# rx08-vrs.net
KiCad netlist of a schematic drawn in EAGLE
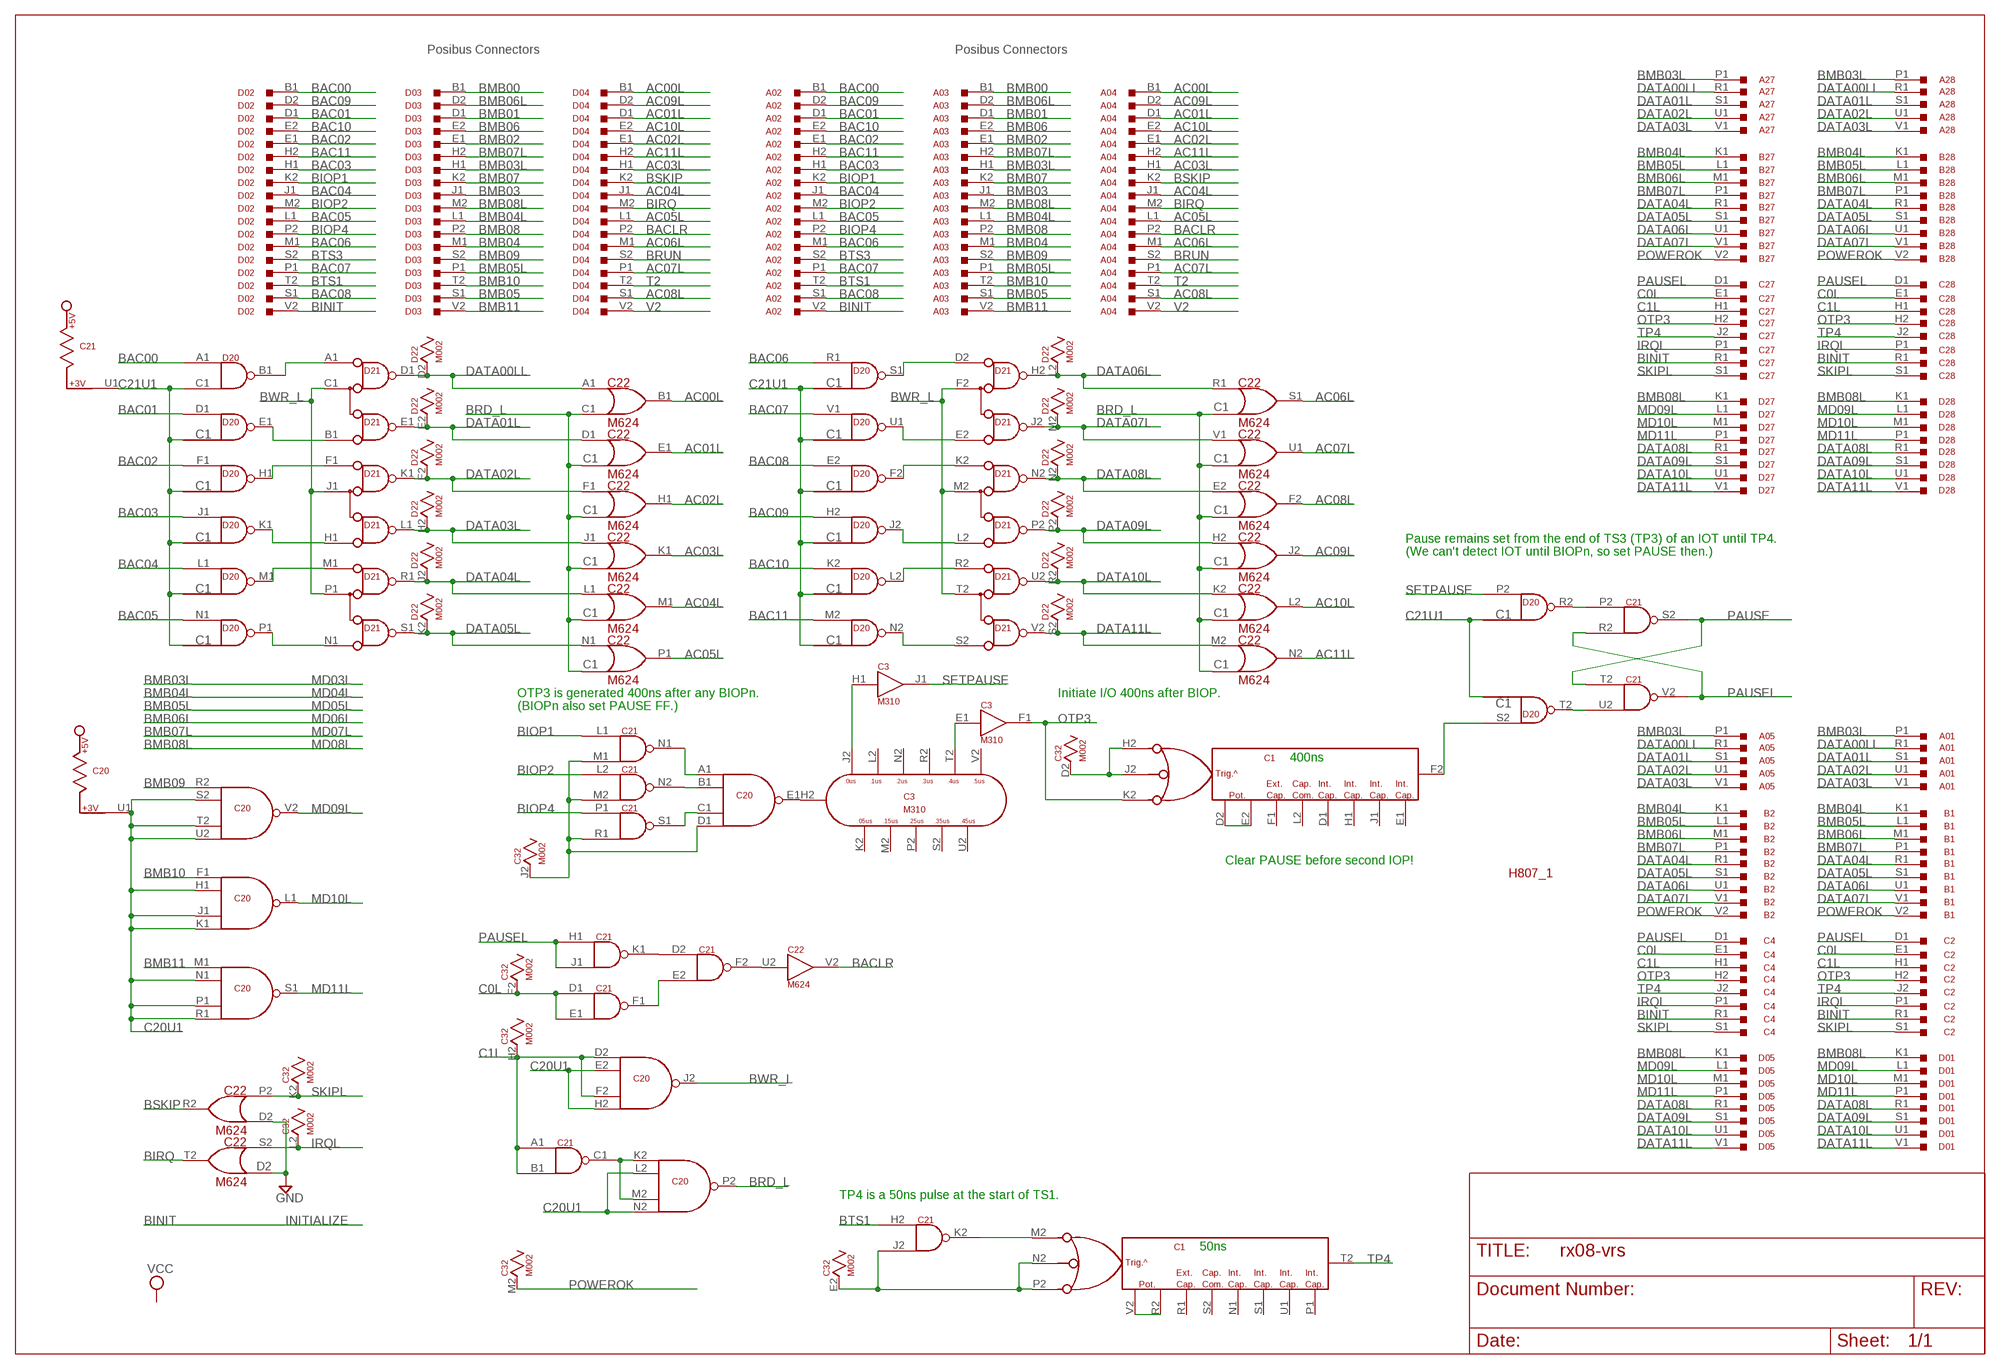
[diagram p0: schematic, sheet 1]

(export (version "E")
  (design (tool "Eeschema 10.0.6"))
  (components
    (comp (ref "A01")
      (value "M916")
      (footprint "eagle-import:H807")
      (libsource (lib "eagle-import") (part "M916"))
    )
    (comp (ref "A02")
      (value "M903")
      (footprint "eagle-import:H807")
      (libsource (lib "eagle-import") (part "M903"))
    )
    (comp (ref "A03")
      (value "M903")
      (footprint "eagle-import:H807")
      (libsource (lib "eagle-import") (part "M903"))
    )
    (comp (ref "A04")
      (value "M903")
      (footprint "eagle-import:H807")
      (libsource (lib "eagle-import") (part "M903"))
    )
    (comp (ref "A05")
      (value "M916")
      (footprint "eagle-import:H807")
      (libsource (lib "eagle-import") (part "M916"))
    )
    (comp (ref "A27")
      (value "M916")
      (footprint "eagle-import:H807")
      (libsource (lib "eagle-import") (part "M916"))
    )
    (comp (ref "A28")
      (value "M916")
      (footprint "eagle-import:H807")
      (libsource (lib "eagle-import") (part "M916"))
    )
    (comp (ref "B1")
      (value "M916")
      (footprint "eagle-import:H807")
      (libsource (lib "eagle-import") (part "M916"))
    )
    (comp (ref "B2")
      (value "M916")
      (footprint "eagle-import:H807")
      (libsource (lib "eagle-import") (part "M916"))
    )
    (comp (ref "B27")
      (value "M916")
      (footprint "eagle-import:H807")
      (libsource (lib "eagle-import") (part "M916"))
    )
    (comp (ref "B28")
      (value "M916")
      (footprint "eagle-import:H807")
      (libsource (lib "eagle-import") (part "M916"))
    )
    (comp (ref "C1")
      (value "M302")
      (footprint "eagle-import:H807")
      (libsource (lib "eagle-import") (part "M302"))
    )
    (comp (ref "C2")
      (value "M916")
      (footprint "eagle-import:H807")
      (libsource (lib "eagle-import") (part "M916"))
    )
    (comp (ref "C3")
      (value "M310")
      (footprint "eagle-import:H807")
      (libsource (lib "eagle-import") (part "M310"))
    )
    (comp (ref "C4")
      (value "M916")
      (footprint "eagle-import:H807")
      (libsource (lib "eagle-import") (part "M916"))
    )
    (comp (ref "C20")
      (value "M617")
      (footprint "eagle-import:H807")
      (libsource (lib "eagle-import") (part "M617"))
    )
    (comp (ref "C21")
      (value "M113")
      (footprint "eagle-import:H807")
      (libsource (lib "eagle-import") (part "M113"))
    )
    (comp (ref "C22")
      (value "M624")
      (footprint "eagle-import:H807")
      (libsource (lib "eagle-import") (part "M624"))
    )
    (comp (ref "C27")
      (value "M916")
      (footprint "eagle-import:H807")
      (libsource (lib "eagle-import") (part "M916"))
    )
    (comp (ref "C28")
      (value "M916")
      (footprint "eagle-import:H807")
      (libsource (lib "eagle-import") (part "M916"))
    )
    (comp (ref "C32")
      (value "M002")
      (footprint "eagle-import:H807")
      (libsource (lib "eagle-import") (part "M002"))
    )
    (comp (ref "D01")
      (value "M916")
      (footprint "eagle-import:H807")
      (libsource (lib "eagle-import") (part "M916"))
    )
    (comp (ref "D02")
      (value "M903")
      (footprint "eagle-import:H807")
      (libsource (lib "eagle-import") (part "M903"))
    )
    (comp (ref "D03")
      (value "M903")
      (footprint "eagle-import:H807")
      (libsource (lib "eagle-import") (part "M903"))
    )
    (comp (ref "D04")
      (value "M903")
      (footprint "eagle-import:H807")
      (libsource (lib "eagle-import") (part "M903"))
    )
    (comp (ref "D05")
      (value "M916")
      (footprint "eagle-import:H807")
      (libsource (lib "eagle-import") (part "M916"))
    )
    (comp (ref "D20")
      (value "M101")
      (footprint "eagle-import:H807")
      (libsource (lib "eagle-import") (part "M101"))
    )
    (comp (ref "D21")
      (value "M623")
      (footprint "eagle-import:H807")
      (libsource (lib "eagle-import") (part "M623"))
    )
    (comp (ref "D22")
      (value "M002")
      (footprint "eagle-import:H807")
      (libsource (lib "eagle-import") (part "M002"))
    )
    (comp (ref "D27")
      (value "M916")
      (footprint "eagle-import:H807")
      (libsource (lib "eagle-import") (part "M916"))
    )
    (comp (ref "D28")
      (value "M916")
      (footprint "eagle-import:H807")
      (libsource (lib "eagle-import") (part "M916"))
    )
    (comp (ref "H807_1")
      (value "H807")
      (footprint "eagle-import:H807")
      (libsource (lib "eagle-import") (part "H807"))
    )
  )
  (nets
    (net (code "1") (name "/AC00L") (class "Default")
      (node (ref "A04") (pin "B1") (pinfunction "P$2_B1") (pintype "bidirectional"))
      (node (ref "C22") (pin "B1") (pinfunction "OUT_B1") (pintype "output"))
      (node (ref "D04") (pin "B1") (pinfunction "P$2_B1") (pintype "bidirectional"))
    )
    (net (code "2") (name "/AC01L") (class "Default")
      (node (ref "A04") (pin "D1") (pinfunction "P$2_D1") (pintype "bidirectional"))
      (node (ref "C22") (pin "E1") (pinfunction "OUT_E1") (pintype "output"))
      (node (ref "D04") (pin "D1") (pinfunction "P$2_D1") (pintype "bidirectional"))
    )
    (net (code "3") (name "/AC02L") (class "Default")
      (node (ref "A04") (pin "E1") (pinfunction "P$2_E1") (pintype "bidirectional"))
      (node (ref "C22") (pin "H1") (pinfunction "OUT_H1") (pintype "output"))
      (node (ref "D04") (pin "E1") (pinfunction "P$2_E1") (pintype "bidirectional"))
    )
    (net (code "4") (name "/AC03L") (class "Default")
      (node (ref "A04") (pin "H1") (pinfunction "P$2_H1") (pintype "bidirectional"))
      (node (ref "C22") (pin "K1") (pinfunction "OUT_K1") (pintype "output"))
      (node (ref "D04") (pin "H1") (pinfunction "P$2_H1") (pintype "bidirectional"))
    )
    (net (code "5") (name "/AC04L") (class "Default")
      (node (ref "A04") (pin "J1") (pinfunction "P$2_J1") (pintype "bidirectional"))
      (node (ref "C22") (pin "M1") (pinfunction "OUT_M1") (pintype "output"))
      (node (ref "D04") (pin "J1") (pinfunction "P$2_J1") (pintype "bidirectional"))
    )
    (net (code "6") (name "/AC05L") (class "Default")
      (node (ref "A04") (pin "L1") (pinfunction "P$2_L1") (pintype "bidirectional"))
      (node (ref "C22") (pin "P1") (pinfunction "OUT_P1") (pintype "output"))
      (node (ref "D04") (pin "L1") (pinfunction "P$2_L1") (pintype "bidirectional"))
    )
    (net (code "7") (name "/AC06L") (class "Default")
      (node (ref "A04") (pin "M1") (pinfunction "P$2_M1") (pintype "bidirectional"))
      (node (ref "C22") (pin "S1") (pinfunction "OUT_S1") (pintype "output"))
      (node (ref "D04") (pin "M1") (pinfunction "P$2_M1") (pintype "bidirectional"))
    )
    (net (code "8") (name "/AC07L") (class "Default")
      (node (ref "A04") (pin "P1") (pinfunction "P$2_P1") (pintype "bidirectional"))
      (node (ref "C22") (pin "U1") (pinfunction "OUT_U1") (pintype "output"))
      (node (ref "D04") (pin "P1") (pinfunction "P$2_P1") (pintype "bidirectional"))
    )
    (net (code "9") (name "/AC08L") (class "Default")
      (node (ref "A04") (pin "S1") (pinfunction "P$2_S1") (pintype "bidirectional"))
      (node (ref "C22") (pin "F2") (pinfunction "OUT_F2") (pintype "output"))
      (node (ref "D04") (pin "S1") (pinfunction "P$2_S1") (pintype "bidirectional"))
    )
    (net (code "10") (name "/AC09L") (class "Default")
      (node (ref "A04") (pin "D2") (pinfunction "P$2_D2") (pintype "bidirectional"))
      (node (ref "C22") (pin "J2") (pinfunction "OUT_J2") (pintype "output"))
      (node (ref "D04") (pin "D2") (pinfunction "P$2_D2") (pintype "bidirectional"))
    )
    (net (code "11") (name "/AC10L") (class "Default")
      (node (ref "A04") (pin "E2") (pinfunction "P$2_E2") (pintype "bidirectional"))
      (node (ref "C22") (pin "L2") (pinfunction "OUT_L2") (pintype "output"))
      (node (ref "D04") (pin "E2") (pinfunction "P$2_E2") (pintype "bidirectional"))
    )
    (net (code "12") (name "/AC11L") (class "Default")
      (node (ref "A04") (pin "H2") (pinfunction "P$2_H2") (pintype "bidirectional"))
      (node (ref "C22") (pin "N2") (pinfunction "OUT_N2") (pintype "output"))
      (node (ref "D04") (pin "H2") (pinfunction "P$2_H2") (pintype "bidirectional"))
    )
    (net (code "13") (name "/BAC00") (class "Default")
      (node (ref "A02") (pin "B1") (pinfunction "P$2_B1") (pintype "bidirectional"))
      (node (ref "D02") (pin "B1") (pinfunction "P$2_B1") (pintype "bidirectional"))
      (node (ref "D20") (pin "A1") (pinfunction "IN1_A1") (pintype "input"))
    )
    (net (code "14") (name "/BAC01") (class "Default")
      (node (ref "A02") (pin "D1") (pinfunction "P$2_D1") (pintype "bidirectional"))
      (node (ref "D02") (pin "D1") (pinfunction "P$2_D1") (pintype "bidirectional"))
      (node (ref "D20") (pin "D1") (pinfunction "IN_D1") (pintype "input"))
    )
    (net (code "15") (name "/BAC02") (class "Default")
      (node (ref "A02") (pin "E1") (pinfunction "P$2_E1") (pintype "bidirectional"))
      (node (ref "D02") (pin "E1") (pinfunction "P$2_E1") (pintype "bidirectional"))
      (node (ref "D20") (pin "F1") (pinfunction "IN_F1") (pintype "input"))
    )
    (net (code "16") (name "/BAC03") (class "Default")
      (node (ref "A02") (pin "H1") (pinfunction "P$2_H1") (pintype "bidirectional"))
      (node (ref "D02") (pin "H1") (pinfunction "P$2_H1") (pintype "bidirectional"))
      (node (ref "D20") (pin "J1") (pinfunction "IN_J1") (pintype "input"))
    )
    (net (code "17") (name "/BAC04") (class "Default")
      (node (ref "A02") (pin "J1") (pinfunction "P$2_J1") (pintype "bidirectional"))
      (node (ref "D02") (pin "J1") (pinfunction "P$2_J1") (pintype "bidirectional"))
      (node (ref "D20") (pin "L1") (pinfunction "IN_L1") (pintype "input"))
    )
    (net (code "18") (name "/BAC05") (class "Default")
      (node (ref "A02") (pin "L1") (pinfunction "P$2_L1") (pintype "bidirectional"))
      (node (ref "D02") (pin "L1") (pinfunction "P$2_L1") (pintype "bidirectional"))
      (node (ref "D20") (pin "N1") (pinfunction "IN_N1") (pintype "input"))
    )
    (net (code "19") (name "/BAC06") (class "Default")
      (node (ref "A02") (pin "M1") (pinfunction "P$2_M1") (pintype "bidirectional"))
      (node (ref "D02") (pin "M1") (pinfunction "P$2_M1") (pintype "bidirectional"))
      (node (ref "D20") (pin "R1") (pinfunction "IN_R1") (pintype "input"))
    )
    (net (code "20") (name "/BAC07") (class "Default")
      (node (ref "A02") (pin "P1") (pinfunction "P$2_P1") (pintype "bidirectional"))
      (node (ref "D02") (pin "P1") (pinfunction "P$2_P1") (pintype "bidirectional"))
      (node (ref "D20") (pin "V1") (pinfunction "IN_V1") (pintype "input"))
    )
    (net (code "21") (name "/BAC08") (class "Default")
      (node (ref "A02") (pin "S1") (pinfunction "P$2_S1") (pintype "bidirectional"))
      (node (ref "D02") (pin "S1") (pinfunction "P$2_S1") (pintype "bidirectional"))
      (node (ref "D20") (pin "E2") (pinfunction "IN_E2") (pintype "input"))
    )
    (net (code "22") (name "/BAC09") (class "Default")
      (node (ref "A02") (pin "D2") (pinfunction "P$2_D2") (pintype "bidirectional"))
      (node (ref "D02") (pin "D2") (pinfunction "P$2_D2") (pintype "bidirectional"))
      (node (ref "D20") (pin "H2") (pinfunction "IN_H2") (pintype "input"))
    )
    (net (code "23") (name "/BAC10") (class "Default")
      (node (ref "A02") (pin "E2") (pinfunction "P$2_E2") (pintype "bidirectional"))
      (node (ref "D02") (pin "E2") (pinfunction "P$2_E2") (pintype "bidirectional"))
      (node (ref "D20") (pin "K2") (pinfunction "IN_K2") (pintype "input"))
    )
    (net (code "24") (name "/BAC11") (class "Default")
      (node (ref "A02") (pin "H2") (pinfunction "P$2_H2") (pintype "bidirectional"))
      (node (ref "D02") (pin "H2") (pinfunction "P$2_H2") (pintype "bidirectional"))
      (node (ref "D20") (pin "M2") (pinfunction "IN_M2") (pintype "input"))
    )
    (net (code "25") (name "/BACLR") (class "Default")
      (node (ref "A04") (pin "P2") (pinfunction "P$2_P2") (pintype "bidirectional"))
      (node (ref "C22") (pin "V2") (pinfunction "OUT_V2") (pintype "output"))
      (node (ref "D04") (pin "P2") (pinfunction "P$2_P2") (pintype "bidirectional"))
    )
    (net (code "26") (name "/BINIT") (class "Default")
      (node (ref "A02") (pin "V2") (pinfunction "P$2_V2") (pintype "bidirectional"))
      (node (ref "C2") (pin "R1") (pinfunction "P$2_R1") (pintype "bidirectional"))
      (node (ref "C27") (pin "R1") (pinfunction "P$2_R1") (pintype "bidirectional"))
      (node (ref "C28") (pin "R1") (pinfunction "P$2_R1") (pintype "bidirectional"))
      (node (ref "C4") (pin "R1") (pinfunction "P$2_R1") (pintype "bidirectional"))
      (node (ref "D02") (pin "V2") (pinfunction "P$2_V2") (pintype "bidirectional"))
    )
    (net (code "27") (name "/BIOP1") (class "Default")
      (node (ref "A02") (pin "K2") (pinfunction "P$2_K2") (pintype "bidirectional"))
      (node (ref "C21") (pin "L1") (pinfunction "IN1_L1") (pintype "input"))
      (node (ref "D02") (pin "K2") (pinfunction "P$2_K2") (pintype "bidirectional"))
    )
    (net (code "28") (name "/BIOP2") (class "Default")
      (node (ref "A02") (pin "M2") (pinfunction "P$2_M2") (pintype "bidirectional"))
      (node (ref "C21") (pin "L2") (pinfunction "IN1_L2") (pintype "input"))
      (node (ref "D02") (pin "M2") (pinfunction "P$2_M2") (pintype "bidirectional"))
    )
    (net (code "29") (name "/BIOP4") (class "Default")
      (node (ref "A02") (pin "P2") (pinfunction "P$2_P2") (pintype "bidirectional"))
      (node (ref "C21") (pin "P1") (pinfunction "IN1_P1") (pintype "input"))
      (node (ref "D02") (pin "P2") (pinfunction "P$2_P2") (pintype "bidirectional"))
    )
    (net (code "30") (name "/BIRQ") (class "Default")
      (node (ref "A04") (pin "M2") (pinfunction "P$2_M2") (pintype "bidirectional"))
      (node (ref "C22") (pin "T2") (pinfunction "OUT_T2") (pintype "output"))
      (node (ref "D04") (pin "M2") (pinfunction "P$2_M2") (pintype "bidirectional"))
    )
    (net (code "31") (name "/BMB00") (class "Default")
      (node (ref "A03") (pin "B1") (pinfunction "P$2_B1") (pintype "bidirectional"))
      (node (ref "D03") (pin "B1") (pinfunction "P$2_B1") (pintype "bidirectional"))
    )
    (net (code "32") (name "/BMB01") (class "Default")
      (node (ref "A03") (pin "D1") (pinfunction "P$2_D1") (pintype "bidirectional"))
      (node (ref "D03") (pin "D1") (pinfunction "P$2_D1") (pintype "bidirectional"))
    )
    (net (code "33") (name "/BMB02") (class "Default")
      (node (ref "A03") (pin "E1") (pinfunction "P$2_E1") (pintype "bidirectional"))
      (node (ref "D03") (pin "E1") (pinfunction "P$2_E1") (pintype "bidirectional"))
    )
    (net (code "34") (name "/BMB03") (class "Default")
      (node (ref "A03") (pin "J1") (pinfunction "P$2_J1") (pintype "bidirectional"))
      (node (ref "D03") (pin "J1") (pinfunction "P$2_J1") (pintype "bidirectional"))
    )
    (net (code "35") (name "/BMB03L") (class "Default")
      (node (ref "A01") (pin "P1") (pinfunction "P$2_P1") (pintype "bidirectional"))
      (node (ref "A03") (pin "H1") (pinfunction "P$2_H1") (pintype "bidirectional"))
      (node (ref "A05") (pin "P1") (pinfunction "P$2_P1") (pintype "bidirectional"))
      (node (ref "A27") (pin "P1") (pinfunction "P$2_P1") (pintype "bidirectional"))
      (node (ref "A28") (pin "P1") (pinfunction "P$2_P1") (pintype "bidirectional"))
      (node (ref "D03") (pin "H1") (pinfunction "P$2_H1") (pintype "bidirectional"))
    )
    (net (code "36") (name "/BMB04") (class "Default")
      (node (ref "A03") (pin "M1") (pinfunction "P$2_M1") (pintype "bidirectional"))
      (node (ref "D03") (pin "M1") (pinfunction "P$2_M1") (pintype "bidirectional"))
    )
    (net (code "37") (name "/BMB04L") (class "Default")
      (node (ref "A03") (pin "L1") (pinfunction "P$2_L1") (pintype "bidirectional"))
      (node (ref "B1") (pin "K1") (pinfunction "P$2_K1") (pintype "bidirectional"))
      (node (ref "B2") (pin "K1") (pinfunction "P$2_K1") (pintype "bidirectional"))
      (node (ref "B27") (pin "K1") (pinfunction "P$2_K1") (pintype "bidirectional"))
      (node (ref "B28") (pin "K1") (pinfunction "P$2_K1") (pintype "bidirectional"))
      (node (ref "D03") (pin "L1") (pinfunction "P$2_L1") (pintype "bidirectional"))
    )
    (net (code "38") (name "/BMB05") (class "Default")
      (node (ref "A03") (pin "S1") (pinfunction "P$2_S1") (pintype "bidirectional"))
      (node (ref "D03") (pin "S1") (pinfunction "P$2_S1") (pintype "bidirectional"))
    )
    (net (code "39") (name "/BMB05L") (class "Default")
      (node (ref "A03") (pin "P1") (pinfunction "P$2_P1") (pintype "bidirectional"))
      (node (ref "B1") (pin "L1") (pinfunction "P$2_L1") (pintype "bidirectional"))
      (node (ref "B2") (pin "L1") (pinfunction "P$2_L1") (pintype "bidirectional"))
      (node (ref "B27") (pin "L1") (pinfunction "P$2_L1") (pintype "bidirectional"))
      (node (ref "B28") (pin "L1") (pinfunction "P$2_L1") (pintype "bidirectional"))
      (node (ref "D03") (pin "P1") (pinfunction "P$2_P1") (pintype "bidirectional"))
    )
    (net (code "40") (name "/BMB06") (class "Default")
      (node (ref "A03") (pin "E2") (pinfunction "P$2_E2") (pintype "bidirectional"))
      (node (ref "D03") (pin "E2") (pinfunction "P$2_E2") (pintype "bidirectional"))
    )
    (net (code "41") (name "/BMB06L") (class "Default")
      (node (ref "A03") (pin "D2") (pinfunction "P$2_D2") (pintype "bidirectional"))
      (node (ref "B1") (pin "M1") (pinfunction "P$2_M1") (pintype "bidirectional"))
      (node (ref "B2") (pin "M1") (pinfunction "P$2_M1") (pintype "bidirectional"))
      (node (ref "B27") (pin "M1") (pinfunction "P$2_M1") (pintype "bidirectional"))
      (node (ref "B28") (pin "M1") (pinfunction "P$2_M1") (pintype "bidirectional"))
      (node (ref "D03") (pin "D2") (pinfunction "P$2_D2") (pintype "bidirectional"))
    )
    (net (code "42") (name "/BMB07") (class "Default")
      (node (ref "A03") (pin "K2") (pinfunction "P$2_K2") (pintype "bidirectional"))
      (node (ref "D03") (pin "K2") (pinfunction "P$2_K2") (pintype "bidirectional"))
    )
    (net (code "43") (name "/BMB07L") (class "Default")
      (node (ref "A03") (pin "H2") (pinfunction "P$2_H2") (pintype "bidirectional"))
      (node (ref "B1") (pin "P1") (pinfunction "P$2_P1") (pintype "bidirectional"))
      (node (ref "B2") (pin "P1") (pinfunction "P$2_P1") (pintype "bidirectional"))
      (node (ref "B27") (pin "P1") (pinfunction "P$2_P1") (pintype "bidirectional"))
      (node (ref "B28") (pin "P1") (pinfunction "P$2_P1") (pintype "bidirectional"))
      (node (ref "D03") (pin "H2") (pinfunction "P$2_H2") (pintype "bidirectional"))
    )
    (net (code "44") (name "/BMB08") (class "Default")
      (node (ref "A03") (pin "P2") (pinfunction "P$2_P2") (pintype "bidirectional"))
      (node (ref "D03") (pin "P2") (pinfunction "P$2_P2") (pintype "bidirectional"))
    )
    (net (code "45") (name "/BMB08L") (class "Default")
      (node (ref "A03") (pin "M2") (pinfunction "P$2_M2") (pintype "bidirectional"))
      (node (ref "D01") (pin "K1") (pinfunction "P$2_K1") (pintype "bidirectional"))
      (node (ref "D03") (pin "M2") (pinfunction "P$2_M2") (pintype "bidirectional"))
      (node (ref "D05") (pin "K1") (pinfunction "P$2_K1") (pintype "bidirectional"))
      (node (ref "D27") (pin "K1") (pinfunction "P$2_K1") (pintype "bidirectional"))
      (node (ref "D28") (pin "K1") (pinfunction "P$2_K1") (pintype "bidirectional"))
    )
    (net (code "46") (name "/BMB09") (class "Default")
      (node (ref "A03") (pin "S2") (pinfunction "P$2_S2") (pintype "bidirectional"))
      (node (ref "C20") (pin "R2") (pinfunction "IN1_R2") (pintype "input"))
      (node (ref "D03") (pin "S2") (pinfunction "P$2_S2") (pintype "bidirectional"))
    )
    (net (code "47") (name "/BMB10") (class "Default")
      (node (ref "A03") (pin "T2") (pinfunction "P$2_T2") (pintype "bidirectional"))
      (node (ref "C20") (pin "F1") (pinfunction "IN1_F1") (pintype "input"))
      (node (ref "D03") (pin "T2") (pinfunction "P$2_T2") (pintype "bidirectional"))
    )
    (net (code "48") (name "/BMB11") (class "Default")
      (node (ref "A03") (pin "V2") (pinfunction "P$2_V2") (pintype "bidirectional"))
      (node (ref "C20") (pin "M1") (pinfunction "IN1_M1") (pintype "input"))
      (node (ref "D03") (pin "V2") (pinfunction "P$2_V2") (pintype "bidirectional"))
    )
    (net (code "49") (name "/BRD_L") (class "Default")
      (node (ref "C20") (pin "P2") (pinfunction "OUT_P2") (pintype "open_collector"))
      (node (ref "C22") (pin "C1") (pinfunction "IN2_C1") (pintype "input"))
    )
    (net (code "50") (name "/BRUN") (class "Default")
      (node (ref "A04") (pin "S2") (pinfunction "P$2_S2") (pintype "bidirectional"))
      (node (ref "D04") (pin "S2") (pinfunction "P$2_S2") (pintype "bidirectional"))
    )
    (net (code "51") (name "/BSKIP") (class "Default")
      (node (ref "A04") (pin "K2") (pinfunction "P$2_K2") (pintype "bidirectional"))
      (node (ref "C22") (pin "R2") (pinfunction "OUT_R2") (pintype "output"))
      (node (ref "D04") (pin "K2") (pinfunction "P$2_K2") (pintype "bidirectional"))
    )
    (net (code "52") (name "/BTS1") (class "Default")
      (node (ref "A02") (pin "T2") (pinfunction "P$2_T2") (pintype "bidirectional"))
      (node (ref "C21") (pin "H2") (pinfunction "IN1_H2") (pintype "input"))
      (node (ref "D02") (pin "T2") (pinfunction "P$2_T2") (pintype "bidirectional"))
    )
    (net (code "53") (name "/BTS3") (class "Default")
      (node (ref "A02") (pin "S2") (pinfunction "P$2_S2") (pintype "bidirectional"))
      (node (ref "D02") (pin "S2") (pinfunction "P$2_S2") (pintype "bidirectional"))
    )
    (net (code "54") (name "/BWR_L") (class "Default")
      (node (ref "C20") (pin "J2") (pinfunction "OUT_J2") (pintype "open_collector"))
      (node (ref "D21") (pin "C1") (pinfunction "C_C1") (pintype "input"))
      (node (ref "D21") (pin "F2") (pinfunction "C_F2") (pintype "input"))
      (node (ref "D21") (pin "J1") (pinfunction "C_J1") (pintype "input"))
      (node (ref "D21") (pin "M2") (pinfunction "C_M2") (pintype "input"))
      (node (ref "D21") (pin "P1") (pinfunction "C_P1") (pintype "input"))
      (node (ref "D21") (pin "T2") (pinfunction "C_T2") (pintype "input"))
    )
    (net (code "55") (name "/C0L") (class "Default")
      (node (ref "C2") (pin "E1") (pinfunction "P$2_E1") (pintype "bidirectional"))
      (node (ref "C21") (pin "D1") (pinfunction "IN1_D1") (pintype "input"))
      (node (ref "C21") (pin "E1") (pinfunction "IN2_E1") (pintype "input"))
      (node (ref "C27") (pin "E1") (pinfunction "P$2_E1") (pintype "bidirectional"))
      (node (ref "C28") (pin "E1") (pinfunction "P$2_E1") (pintype "bidirectional"))
      (node (ref "C32") (pin "F2") (pinfunction "P$1_F2") (pintype "passive"))
      (node (ref "C4") (pin "E1") (pinfunction "P$2_E1") (pintype "bidirectional"))
    )
    (net (code "56") (name "/C1L") (class "Default")
      (node (ref "C2") (pin "H1") (pinfunction "P$2_H1") (pintype "bidirectional"))
      (node (ref "C20") (pin "D2") (pinfunction "IN1_D2") (pintype "input"))
      (node (ref "C20") (pin "F2") (pinfunction "IN3_F2") (pintype "input"))
      (node (ref "C21") (pin "A1") (pinfunction "IN1_A1") (pintype "input"))
      (node (ref "C21") (pin "B1") (pinfunction "IN2_B1") (pintype "input"))
      (node (ref "C27") (pin "H1") (pinfunction "P$2_H1") (pintype "bidirectional"))
      (node (ref "C28") (pin "H1") (pinfunction "P$2_H1") (pintype "bidirectional"))
      (node (ref "C32") (pin "H2") (pinfunction "P$1_H2") (pintype "passive"))
      (node (ref "C4") (pin "H1") (pinfunction "P$2_H1") (pintype "bidirectional"))
    )
    (net (code "57") (name "/C20U1") (class "Default")
      (node (ref "C20") (pin "E2") (pinfunction "IN2_E2") (pintype "input"))
      (node (ref "C20") (pin "H1") (pinfunction "IN2_H1") (pintype "input"))
      (node (ref "C20") (pin "H2") (pinfunction "IN4_H2") (pintype "input"))
      (node (ref "C20") (pin "J1") (pinfunction "IN3_J1") (pintype "input"))
      (node (ref "C20") (pin "K1") (pinfunction "IN4_K1") (pintype "input"))
      (node (ref "C20") (pin "L2") (pinfunction "IN2_L2") (pintype "input"))
      (node (ref "C20") (pin "N1") (pinfunction "IN2_N1") (pintype "input"))
      (node (ref "C20") (pin "N2") (pinfunction "IN4_N2") (pintype "input"))
      (node (ref "C20") (pin "P1") (pinfunction "IN3_P1") (pintype "input"))
      (node (ref "C20") (pin "R1") (pinfunction "IN4_R1") (pintype "input"))
      (node (ref "C20") (pin "S2") (pinfunction "IN2_S2") (pintype "input"))
      (node (ref "C20") (pin "T2") (pinfunction "IN3_T2") (pintype "input"))
      (node (ref "C20") (pin "U1") (pinfunction "P$1_U1") (pintype "passive"))
      (node (ref "C20") (pin "U2") (pinfunction "IN4_U2") (pintype "input"))
    )
    (net (code "58") (name "/C21U1") (class "Default")
      (node (ref "C21") (pin "U1") (pinfunction "P$1_U1") (pintype "passive"))
      (node (ref "D20") (pin "C1") (pinfunction "IN2_C1") (pintype "input"))
    )
    (net (code "59") (name "/DATA00LL") (class "Default")
      (node (ref "A01") (pin "R1") (pinfunction "P$2_R1") (pintype "bidirectional"))
      (node (ref "A05") (pin "R1") (pinfunction "P$2_R1") (pintype "bidirectional"))
      (node (ref "A27") (pin "R1") (pinfunction "P$2_R1") (pintype "bidirectional"))
      (node (ref "A28") (pin "R1") (pinfunction "P$2_R1") (pintype "bidirectional"))
      (node (ref "C22") (pin "A1") (pinfunction "IN1_A1") (pintype "input"))
      (node (ref "D21") (pin "D1") (pinfunction "D_D1") (pintype "open_collector"))
      (node (ref "D22") (pin "D2") (pinfunction "P$1_D2") (pintype "passive"))
    )
    (net (code "60") (name "/DATA01L") (class "Default")
      (node (ref "A01") (pin "S1") (pinfunction "P$2_S1") (pintype "bidirectional"))
      (node (ref "A05") (pin "S1") (pinfunction "P$2_S1") (pintype "bidirectional"))
      (node (ref "A27") (pin "S1") (pinfunction "P$2_S1") (pintype "bidirectional"))
      (node (ref "A28") (pin "S1") (pinfunction "P$2_S1") (pintype "bidirectional"))
      (node (ref "C22") (pin "D1") (pinfunction "IN_D1") (pintype "input"))
      (node (ref "D21") (pin "E1") (pinfunction "E_E1") (pintype "open_collector"))
      (node (ref "D22") (pin "E2") (pinfunction "P$1_E2") (pintype "passive"))
    )
    (net (code "61") (name "/DATA02L") (class "Default")
      (node (ref "A01") (pin "U1") (pinfunction "P$2_U1") (pintype "bidirectional"))
      (node (ref "A05") (pin "U1") (pinfunction "P$2_U1") (pintype "bidirectional"))
      (node (ref "A27") (pin "U1") (pinfunction "P$2_U1") (pintype "bidirectional"))
      (node (ref "A28") (pin "U1") (pinfunction "P$2_U1") (pintype "bidirectional"))
      (node (ref "C22") (pin "F1") (pinfunction "IN_F1") (pintype "input"))
      (node (ref "D21") (pin "K1") (pinfunction "D_K1") (pintype "open_collector"))
      (node (ref "D22") (pin "F2") (pinfunction "P$1_F2") (pintype "passive"))
    )
    (net (code "62") (name "/DATA03L") (class "Default")
      (node (ref "A01") (pin "V1") (pinfunction "P$2_V1") (pintype "bidirectional"))
      (node (ref "A05") (pin "V1") (pinfunction "P$2_V1") (pintype "bidirectional"))
      (node (ref "A27") (pin "V1") (pinfunction "P$2_V1") (pintype "bidirectional"))
      (node (ref "A28") (pin "V1") (pinfunction "P$2_V1") (pintype "bidirectional"))
      (node (ref "C22") (pin "J1") (pinfunction "IN_J1") (pintype "input"))
      (node (ref "D21") (pin "L1") (pinfunction "E_L1") (pintype "open_collector"))
      (node (ref "D22") (pin "H2") (pinfunction "P$1_H2") (pintype "passive"))
    )
    (net (code "63") (name "/DATA04L") (class "Default")
      (node (ref "B1") (pin "R1") (pinfunction "P$2_R1") (pintype "bidirectional"))
      (node (ref "B2") (pin "R1") (pinfunction "P$2_R1") (pintype "bidirectional"))
      (node (ref "B27") (pin "R1") (pinfunction "P$2_R1") (pintype "bidirectional"))
      (node (ref "B28") (pin "R1") (pinfunction "P$2_R1") (pintype "bidirectional"))
      (node (ref "C22") (pin "L1") (pinfunction "IN_L1") (pintype "input"))
      (node (ref "D21") (pin "R1") (pinfunction "D_R1") (pintype "open_collector"))
      (node (ref "D22") (pin "J2") (pinfunction "P$1_J2") (pintype "passive"))
    )
    (net (code "64") (name "/DATA05L") (class "Default")
      (node (ref "B1") (pin "S1") (pinfunction "P$2_S1") (pintype "bidirectional"))
      (node (ref "B2") (pin "S1") (pinfunction "P$2_S1") (pintype "bidirectional"))
      (node (ref "B27") (pin "S1") (pinfunction "P$2_S1") (pintype "bidirectional"))
      (node (ref "B28") (pin "S1") (pinfunction "P$2_S1") (pintype "bidirectional"))
      (node (ref "C22") (pin "N1") (pinfunction "IN_N1") (pintype "input"))
      (node (ref "D21") (pin "S1") (pinfunction "E_S1") (pintype "open_collector"))
      (node (ref "D22") (pin "K2") (pinfunction "P$1_K2") (pintype "passive"))
    )
    (net (code "65") (name "/DATA06L") (class "Default")
      (node (ref "B1") (pin "U1") (pinfunction "P$2_U1") (pintype "bidirectional"))
      (node (ref "B2") (pin "U1") (pinfunction "P$2_U1") (pintype "bidirectional"))
      (node (ref "B27") (pin "U1") (pinfunction "P$2_U1") (pintype "bidirectional"))
      (node (ref "B28") (pin "U1") (pinfunction "P$2_U1") (pintype "bidirectional"))
      (node (ref "C22") (pin "R1") (pinfunction "IN_R1") (pintype "input"))
      (node (ref "D21") (pin "H2") (pinfunction "D_H2") (pintype "open_collector"))
      (node (ref "D22") (pin "L2") (pinfunction "P$1_L2") (pintype "passive"))
    )
    (net (code "66") (name "/DATA07L") (class "Default")
      (node (ref "B1") (pin "V1") (pinfunction "P$2_V1") (pintype "bidirectional"))
      (node (ref "B2") (pin "V1") (pinfunction "P$2_V1") (pintype "bidirectional"))
      (node (ref "B27") (pin "V1") (pinfunction "P$2_V1") (pintype "bidirectional"))
      (node (ref "B28") (pin "V1") (pinfunction "P$2_V1") (pintype "bidirectional"))
      (node (ref "C22") (pin "V1") (pinfunction "IN_V1") (pintype "input"))
      (node (ref "D21") (pin "J2") (pinfunction "E_J2") (pintype "open_collector"))
      (node (ref "D22") (pin "M2") (pinfunction "P$1_M2") (pintype "passive"))
    )
    (net (code "67") (name "/DATA08L") (class "Default")
      (node (ref "C22") (pin "E2") (pinfunction "IN_E2") (pintype "input"))
      (node (ref "D01") (pin "R1") (pinfunction "P$2_R1") (pintype "bidirectional"))
      (node (ref "D05") (pin "R1") (pinfunction "P$2_R1") (pintype "bidirectional"))
      (node (ref "D21") (pin "N2") (pinfunction "D_N2") (pintype "open_collector"))
      (node (ref "D22") (pin "N2") (pinfunction "P$1_N2") (pintype "passive"))
      (node (ref "D27") (pin "R1") (pinfunction "P$2_R1") (pintype "bidirectional"))
      (node (ref "D28") (pin "R1") (pinfunction "P$2_R1") (pintype "bidirectional"))
    )
    (net (code "68") (name "/DATA09L") (class "Default")
      (node (ref "C22") (pin "H2") (pinfunction "IN_H2") (pintype "input"))
      (node (ref "D01") (pin "S1") (pinfunction "P$2_S1") (pintype "bidirectional"))
      (node (ref "D05") (pin "S1") (pinfunction "P$2_S1") (pintype "bidirectional"))
      (node (ref "D21") (pin "P2") (pinfunction "E_P2") (pintype "open_collector"))
      (node (ref "D22") (pin "P2") (pinfunction "P$1_P2") (pintype "passive"))
      (node (ref "D27") (pin "S1") (pinfunction "P$2_S1") (pintype "bidirectional"))
      (node (ref "D28") (pin "S1") (pinfunction "P$2_S1") (pintype "bidirectional"))
    )
    (net (code "69") (name "/DATA10L") (class "Default")
      (node (ref "C22") (pin "K2") (pinfunction "IN_K2") (pintype "input"))
      (node (ref "D01") (pin "U1") (pinfunction "P$2_U1") (pintype "bidirectional"))
      (node (ref "D05") (pin "U1") (pinfunction "P$2_U1") (pintype "bidirectional"))
      (node (ref "D21") (pin "U2") (pinfunction "D_U2") (pintype "open_collector"))
      (node (ref "D22") (pin "R2") (pinfunction "P$1_R2") (pintype "passive"))
      (node (ref "D27") (pin "U1") (pinfunction "P$2_U1") (pintype "bidirectional"))
      (node (ref "D28") (pin "U1") (pinfunction "P$2_U1") (pintype "bidirectional"))
    )
    (net (code "70") (name "/DATA11L") (class "Default")
      (node (ref "C22") (pin "M2") (pinfunction "IN_M2") (pintype "input"))
      (node (ref "D01") (pin "V1") (pinfunction "P$2_V1") (pintype "bidirectional"))
      (node (ref "D05") (pin "V1") (pinfunction "P$2_V1") (pintype "bidirectional"))
      (node (ref "D21") (pin "V2") (pinfunction "E_V2") (pintype "open_collector"))
      (node (ref "D22") (pin "S2") (pinfunction "P$1_S2") (pintype "passive"))
      (node (ref "D27") (pin "V1") (pinfunction "P$2_V1") (pintype "bidirectional"))
      (node (ref "D28") (pin "V1") (pinfunction "P$2_V1") (pintype "bidirectional"))
    )
    (net (code "71") (name "/IRQL") (class "Default")
      (node (ref "C2") (pin "P1") (pinfunction "P$2_P1") (pintype "bidirectional"))
      (node (ref "C22") (pin "S2") (pinfunction "IN_S2") (pintype "input"))
      (node (ref "C27") (pin "P1") (pinfunction "P$2_P1") (pintype "bidirectional"))
      (node (ref "C28") (pin "P1") (pinfunction "P$2_P1") (pintype "bidirectional"))
      (node (ref "C32") (pin "L2") (pinfunction "P$1_L2") (pintype "passive"))
      (node (ref "C4") (pin "P1") (pinfunction "P$2_P1") (pintype "bidirectional"))
    )
    (net (code "72") (name "/MD09L") (class "Default")
      (node (ref "C20") (pin "V2") (pinfunction "OUT_V2") (pintype "open_collector"))
      (node (ref "D01") (pin "L1") (pinfunction "P$2_L1") (pintype "bidirectional"))
      (node (ref "D05") (pin "L1") (pinfunction "P$2_L1") (pintype "bidirectional"))
      (node (ref "D27") (pin "L1") (pinfunction "P$2_L1") (pintype "bidirectional"))
      (node (ref "D28") (pin "L1") (pinfunction "P$2_L1") (pintype "bidirectional"))
    )
    (net (code "73") (name "/MD10L") (class "Default")
      (node (ref "C20") (pin "L1") (pinfunction "OUT_L1") (pintype "open_collector"))
      (node (ref "D01") (pin "M1") (pinfunction "P$2_M1") (pintype "bidirectional"))
      (node (ref "D05") (pin "M1") (pinfunction "P$2_M1") (pintype "bidirectional"))
      (node (ref "D27") (pin "M1") (pinfunction "P$2_M1") (pintype "bidirectional"))
      (node (ref "D28") (pin "M1") (pinfunction "P$2_M1") (pintype "bidirectional"))
    )
    (net (code "74") (name "/MD11L") (class "Default")
      (node (ref "C20") (pin "S1") (pinfunction "OUT_S1") (pintype "open_collector"))
      (node (ref "D01") (pin "P1") (pinfunction "P$2_P1") (pintype "bidirectional"))
      (node (ref "D05") (pin "P1") (pinfunction "P$2_P1") (pintype "bidirectional"))
      (node (ref "D27") (pin "P1") (pinfunction "P$2_P1") (pintype "bidirectional"))
      (node (ref "D28") (pin "P1") (pinfunction "P$2_P1") (pintype "bidirectional"))
    )
    (net (code "75") (name "/OTP3") (class "Default")
      (node (ref "C1") (pin "K2") (pinfunction "K2_K2") (pintype "input"))
      (node (ref "C2") (pin "H2") (pinfunction "P$2_H2") (pintype "bidirectional"))
      (node (ref "C27") (pin "H2") (pinfunction "P$2_H2") (pintype "bidirectional"))
      (node (ref "C28") (pin "H2") (pinfunction "P$2_H2") (pintype "bidirectional"))
      (node (ref "C3") (pin "F1") (pinfunction "OUT_F1") (pintype "output"))
      (node (ref "C4") (pin "H2") (pinfunction "P$2_H2") (pintype "bidirectional"))
    )
    (net (code "76") (name "/PAUSE") (class "Default")
      (node (ref "C21") (pin "S2") (pinfunction "OUT_S2") (pintype "output"))
      (node (ref "C21") (pin "T2") (pinfunction "IN1_T2") (pintype "input"))
    )
    (net (code "77") (name "/PAUSEL") (class "Default")
      (node (ref "C2") (pin "D1") (pinfunction "P$2_D1") (pintype "bidirectional"))
      (node (ref "C21") (pin "H1") (pinfunction "IN1_H1") (pintype "input"))
      (node (ref "C21") (pin "J1") (pinfunction "IN2_J1") (pintype "input"))
      (node (ref "C21") (pin "R2") (pinfunction "IN2_R2") (pintype "input"))
      (node (ref "C21") (pin "V2") (pinfunction "OUT_V2") (pintype "output"))
      (node (ref "C27") (pin "D1") (pinfunction "P$2_D1") (pintype "bidirectional"))
      (node (ref "C28") (pin "D1") (pinfunction "P$2_D1") (pintype "bidirectional"))
      (node (ref "C4") (pin "D1") (pinfunction "P$2_D1") (pintype "bidirectional"))
    )
    (net (code "78") (name "/POWEROK") (class "Default")
      (node (ref "B1") (pin "V2") (pinfunction "P$2_V2") (pintype "bidirectional"))
      (node (ref "B2") (pin "V2") (pinfunction "P$2_V2") (pintype "bidirectional"))
      (node (ref "B27") (pin "V2") (pinfunction "P$2_V2") (pintype "bidirectional"))
      (node (ref "B28") (pin "V2") (pinfunction "P$2_V2") (pintype "bidirectional"))
      (node (ref "C32") (pin "M2") (pinfunction "P$1_M2") (pintype "passive"))
    )
    (net (code "79") (name "/SETPAUSE") (class "Default")
      (node (ref "C3") (pin "J1") (pinfunction "OUT_J1") (pintype "output"))
      (node (ref "D20") (pin "P2") (pinfunction "IN_P2") (pintype "input"))
    )
    (net (code "80") (name "/SKIPL") (class "Default")
      (node (ref "C2") (pin "S1") (pinfunction "P$2_S1") (pintype "bidirectional"))
      (node (ref "C22") (pin "P2") (pinfunction "IN1_P2") (pintype "input"))
      (node (ref "C27") (pin "S1") (pinfunction "P$2_S1") (pintype "bidirectional"))
      (node (ref "C28") (pin "S1") (pinfunction "P$2_S1") (pintype "bidirectional"))
      (node (ref "C32") (pin "K2") (pinfunction "P$1_K2") (pintype "passive"))
      (node (ref "C4") (pin "S1") (pinfunction "P$2_S1") (pintype "bidirectional"))
    )
    (net (code "81") (name "/T2") (class "Default")
      (node (ref "A04") (pin "T2") (pinfunction "P$2_T2") (pintype "bidirectional"))
      (node (ref "D04") (pin "T2") (pinfunction "P$2_T2") (pintype "bidirectional"))
    )
    (net (code "82") (name "/TP4") (class "Default")
      (node (ref "C1") (pin "T2") (pinfunction "F2_T2") (pintype "output"))
      (node (ref "C2") (pin "J2") (pinfunction "P$2_J2") (pintype "bidirectional"))
      (node (ref "C27") (pin "J2") (pinfunction "P$2_J2") (pintype "bidirectional"))
      (node (ref "C28") (pin "J2") (pinfunction "P$2_J2") (pintype "bidirectional"))
      (node (ref "C4") (pin "J2") (pinfunction "P$2_J2") (pintype "bidirectional"))
    )
    (net (code "83") (name "/V2") (class "Default")
      (node (ref "A04") (pin "V2") (pinfunction "P$2_V2") (pintype "bidirectional"))
      (node (ref "D04") (pin "V2") (pinfunction "P$2_V2") (pintype "bidirectional"))
    )
    (net (code "84") (name "GND") (class "Default")
      (node (ref "C22") (pin "D2") (pinfunction "IN2_D2") (pintype "input"))
    )
    (net (code "85") (name "Net-(C1-PadD2)") (class "Default")
      (node (ref "C1") (pin "D2") (pinfunction "D2_D2") (pintype "passive"))
      (node (ref "C1") (pin "E2") (pinfunction "E2_E2") (pintype "passive"))
    )
    (net (code "86") (name "Net-(C1D-D2)") (class "Default")
      (node (ref "C1") (pin "R2") (pinfunction "E2_R2") (pintype "passive"))
      (node (ref "C1") (pin "V2") (pinfunction "D2_V2") (pintype "passive"))
    )
    (net (code "87") (name "Net-(C1D-H2)") (class "Default")
      (node (ref "C1") (pin "M2") (pinfunction "H2_M2") (pintype "input"))
      (node (ref "C21") (pin "K2") (pinfunction "OUT_K2") (pintype "output"))
    )
    (net (code "88") (name "Net-(C1D-J2)") (class "Default")
      (node (ref "C1") (pin "N2") (pinfunction "J2_N2") (pintype "input"))
      (node (ref "C1") (pin "P2") (pinfunction "K2_P2") (pintype "input"))
      (node (ref "C21") (pin "J2") (pinfunction "IN2_J2") (pintype "input"))
      (node (ref "C32") (pin "E2") (pinfunction "P$1_E2") (pintype "passive"))
    )
    (net (code "89") (name "Net-(C3A-IN)") (class "Default")
      (node (ref "C3") (pin "E1") (pinfunction "IN_E1") (pintype "input"))
      (node (ref "C3") (pin "T2") (pinfunction "T2_T2") (pintype "output"))
    )
    (net (code "90") (name "Net-(C3E-IN)") (class "Default")
      (node (ref "C3") (pin "H1") (pinfunction "IN_H1") (pintype "input"))
      (node (ref "C3") (pin "J2") (pinfunction "J2_J2") (pintype "output"))
    )
    (net (code "91") (name "Net-(C20A-IN1)") (class "Default")
      (node (ref "C20") (pin "A1") (pinfunction "IN1_A1") (pintype "input"))
      (node (ref "C21") (pin "N1") (pinfunction "OUT_N1") (pintype "output"))
    )
    (net (code "92") (name "Net-(C20A-IN2)") (class "Default")
      (node (ref "C20") (pin "B1") (pinfunction "IN2_B1") (pintype "input"))
      (node (ref "C21") (pin "N2") (pinfunction "OUT_N2") (pintype "output"))
    )
    (net (code "93") (name "Net-(C20A-IN3)") (class "Default")
      (node (ref "C20") (pin "C1") (pinfunction "IN3_C1") (pintype "input"))
      (node (ref "C21") (pin "S1") (pinfunction "OUT_S1") (pintype "output"))
    )
    (net (code "94") (name "Net-(C20A-IN4)") (class "Default")
      (node (ref "C20") (pin "D1") (pinfunction "IN4_D1") (pintype "input"))
      (node (ref "C21") (pin "M1") (pinfunction "IN2_M1") (pintype "input"))
      (node (ref "C21") (pin "M2") (pinfunction "IN2_M2") (pintype "input"))
      (node (ref "C21") (pin "R1") (pinfunction "IN2_R1") (pintype "input"))
      (node (ref "C32") (pin "J2") (pinfunction "P$1_J2") (pintype "passive"))
    )
    (net (code "95") (name "Net-(C20A-OUT)") (class "Default")
      (node (ref "C20") (pin "E1") (pinfunction "OUT_E1") (pintype "open_collector"))
      (node (ref "C3") (pin "H2") (pinfunction "H2_H2") (pintype "input"))
    )
    (net (code "96") (name "Net-(C20F-IN1)") (class "Default")
      (node (ref "C20") (pin "K2") (pinfunction "IN1_K2") (pintype "input"))
      (node (ref "C20") (pin "M2") (pinfunction "IN3_M2") (pintype "input"))
      (node (ref "C21") (pin "C1") (pinfunction "OUT_C1") (pintype "output"))
    )
    (net (code "97") (name "Net-(C21B-OUT)") (class "Default")
      (node (ref "C21") (pin "E2") (pinfunction "IN2_E2") (pintype "input"))
      (node (ref "C21") (pin "F1") (pinfunction "OUT_F1") (pintype "output"))
    )
    (net (code "98") (name "Net-(C21C-IN1)") (class "Default")
      (node (ref "C21") (pin "D2") (pinfunction "IN1_D2") (pintype "input"))
      (node (ref "C21") (pin "K1") (pinfunction "OUT_K1") (pintype "output"))
    )
    (net (code "99") (name "Net-(C21C-OUT)") (class "Default")
      (node (ref "C21") (pin "F2") (pinfunction "OUT_F2") (pintype "output"))
      (node (ref "C22") (pin "U2") (pinfunction "IN_U2") (pintype "input"))
    )
    (net (code "100") (name "Net-(C21K-IN1)") (class "Default")
      (node (ref "C21") (pin "P2") (pinfunction "IN1_P2") (pintype "input"))
      (node (ref "D20") (pin "R2") (pinfunction "OUT_R2") (pintype "output"))
    )
    (net (code "101") (name "Net-(C21N-IN2)") (class "Default")
      (node (ref "C21") (pin "U2") (pinfunction "IN2_U2") (pintype "input"))
      (node (ref "D20") (pin "T2") (pinfunction "OUT_T2") (pintype "output"))
    )
    (net (code "102") (name "Net-(C32A-P$1)") (class "Default")
      (node (ref "C1") (pin "H2") (pinfunction "H2_H2") (pintype "input"))
      (node (ref "C1") (pin "J2") (pinfunction "J2_J2") (pintype "input"))
      (node (ref "C32") (pin "D2") (pinfunction "P$1_D2") (pintype "passive"))
    )
    (net (code "103") (name "Net-(D20A-OUT)") (class "Default")
      (node (ref "D20") (pin "B1") (pinfunction "OUT_B1") (pintype "output"))
      (node (ref "D21") (pin "A1") (pinfunction "A_A1") (pintype "input"))
    )
    (net (code "104") (name "Net-(D20B-OUT)") (class "Default")
      (node (ref "D20") (pin "E1") (pinfunction "OUT_E1") (pintype "output"))
      (node (ref "D21") (pin "B1") (pinfunction "B_B1") (pintype "input"))
    )
    (net (code "105") (name "Net-(D20C-OUT)") (class "Default")
      (node (ref "D20") (pin "F2") (pinfunction "OUT_F2") (pintype "output"))
      (node (ref "D21") (pin "K2") (pinfunction "A_K2") (pintype "input"))
    )
    (net (code "106") (name "Net-(D20F-OUT)") (class "Default")
      (node (ref "D20") (pin "H1") (pinfunction "OUT_H1") (pintype "output"))
      (node (ref "D21") (pin "F1") (pinfunction "A_F1") (pintype "input"))
    )
    (net (code "107") (name "Net-(D20G-OUT)") (class "Default")
      (node (ref "D20") (pin "J2") (pinfunction "OUT_J2") (pintype "output"))
      (node (ref "D21") (pin "L2") (pinfunction "B_L2") (pintype "input"))
    )
    (net (code "108") (name "Net-(D20H-OUT)") (class "Default")
      (node (ref "D20") (pin "K1") (pinfunction "OUT_K1") (pintype "output"))
      (node (ref "D21") (pin "H1") (pinfunction "B_H1") (pintype "input"))
    )
    (net (code "109") (name "Net-(D20I-OUT)") (class "Default")
      (node (ref "D20") (pin "L2") (pinfunction "OUT_L2") (pintype "output"))
      (node (ref "D21") (pin "R2") (pinfunction "A_R2") (pintype "input"))
    )
    (net (code "110") (name "Net-(D20J-OUT)") (class "Default")
      (node (ref "D20") (pin "M1") (pinfunction "OUT_M1") (pintype "output"))
      (node (ref "D21") (pin "M1") (pinfunction "A_M1") (pintype "input"))
    )
    (net (code "111") (name "Net-(D20K-OUT)") (class "Default")
      (node (ref "D20") (pin "N2") (pinfunction "OUT_N2") (pintype "output"))
      (node (ref "D21") (pin "S2") (pinfunction "B_S2") (pintype "input"))
    )
    (net (code "112") (name "Net-(D20L-OUT)") (class "Default")
      (node (ref "D20") (pin "P1") (pinfunction "OUT_P1") (pintype "output"))
      (node (ref "D21") (pin "N1") (pinfunction "B_N1") (pintype "input"))
    )
    (net (code "113") (name "Net-(D20N-OUT)") (class "Default")
      (node (ref "D20") (pin "S1") (pinfunction "OUT_S1") (pintype "output"))
      (node (ref "D21") (pin "D2") (pinfunction "A_D2") (pintype "input"))
    )
    (net (code "114") (name "Net-(D20O-IN)") (class "Default")
      (node (ref "C1") (pin "F2") (pinfunction "F2_F2") (pintype "output"))
      (node (ref "D20") (pin "S2") (pinfunction "IN_S2") (pintype "input"))
    )
    (net (code "115") (name "Net-(D20P-OUT)") (class "Default")
      (node (ref "D20") (pin "U1") (pinfunction "OUT_U1") (pintype "output"))
      (node (ref "D21") (pin "E2") (pinfunction "B_E2") (pintype "input"))
    )
    (net (code "117") (name "unconnected-(C1-PadD1)") (class "Default")
      (node (ref "C1") (pin "D1") (pinfunction "D1_D1") (pintype "passive"))
    )
    (net (code "118") (name "unconnected-(C1-PadE1)") (class "Default")
      (node (ref "C1") (pin "E1") (pinfunction "E1_E1") (pintype "passive"))
    )
    (net (code "119") (name "unconnected-(C1-PadF1)") (class "Default")
      (node (ref "C1") (pin "F1") (pinfunction "F1_F1") (pintype "passive"))
    )
    (net (code "120") (name "unconnected-(C1-PadH1)") (class "Default")
      (node (ref "C1") (pin "H1") (pinfunction "H1_H1") (pintype "passive"))
    )
    (net (code "121") (name "unconnected-(C1-PadJ1)") (class "Default")
      (node (ref "C1") (pin "J1") (pinfunction "J1_J1") (pintype "passive"))
    )
    (net (code "122") (name "unconnected-(C1-PadL2)") (class "Default")
      (node (ref "C1") (pin "L2") (pinfunction "L2_L2") (pintype "passive"))
    )
    (net (code "123") (name "unconnected-(C1D-D1-PadN1)") (class "Default")
      (node (ref "C1") (pin "N1") (pinfunction "D1_N1") (pintype "passive"))
    )
    (net (code "124") (name "unconnected-(C1D-E1-PadP1)") (class "Default")
      (node (ref "C1") (pin "P1") (pinfunction "E1_P1") (pintype "passive"))
    )
    (net (code "125") (name "unconnected-(C1D-F1-PadR1)") (class "Default")
      (node (ref "C1") (pin "R1") (pinfunction "F1_R1") (pintype "passive"))
    )
    (net (code "126") (name "unconnected-(C1D-H1-PadS1)") (class "Default")
      (node (ref "C1") (pin "S1") (pinfunction "H1_S1") (pintype "passive"))
    )
    (net (code "127") (name "unconnected-(C1D-J1-PadU1)") (class "Default")
      (node (ref "C1") (pin "U1") (pinfunction "J1_U1") (pintype "passive"))
    )
    (net (code "128") (name "unconnected-(C1D-L2-PadS2)") (class "Default")
      (node (ref "C1") (pin "S2") (pinfunction "L2_S2") (pintype "passive"))
    )
    (net (code "129") (name "unconnected-(C3-PadK2)") (class "Default")
      (node (ref "C3") (pin "K2") (pinfunction "K2_K2") (pintype "output"))
    )
    (net (code "130") (name "unconnected-(C3-PadL2)") (class "Default")
      (node (ref "C3") (pin "L2") (pinfunction "L2_L2") (pintype "output"))
    )
    (net (code "131") (name "unconnected-(C3-PadM2)") (class "Default")
      (node (ref "C3") (pin "M2") (pinfunction "M2_M2") (pintype "output"))
    )
    (net (code "132") (name "unconnected-(C3-PadN2)") (class "Default")
      (node (ref "C3") (pin "N2") (pinfunction "N2_N2") (pintype "output"))
    )
    (net (code "133") (name "unconnected-(C3-PadP2)") (class "Default")
      (node (ref "C3") (pin "P2") (pinfunction "P2_P2") (pintype "output"))
    )
    (net (code "134") (name "unconnected-(C3-PadR2)") (class "Default")
      (node (ref "C3") (pin "R2") (pinfunction "R2_R2") (pintype "output"))
    )
    (net (code "135") (name "unconnected-(C3-PadS2)") (class "Default")
      (node (ref "C3") (pin "S2") (pinfunction "S2_S2") (pintype "output"))
    )
    (net (code "136") (name "unconnected-(C3-PadU2)") (class "Default")
      (node (ref "C3") (pin "U2") (pinfunction "U2_U2") (pintype "output"))
    )
    (net (code "137") (name "unconnected-(C3-PadV2)") (class "Default")
      (node (ref "C3") (pin "V2") (pinfunction "V2_V2") (pintype "output"))
    )
  )
)
